# Own_Power_Measuring_Bridge_dev_v1_0_Fina.net
KiCad netlist of a schematic drawn in EAGLE
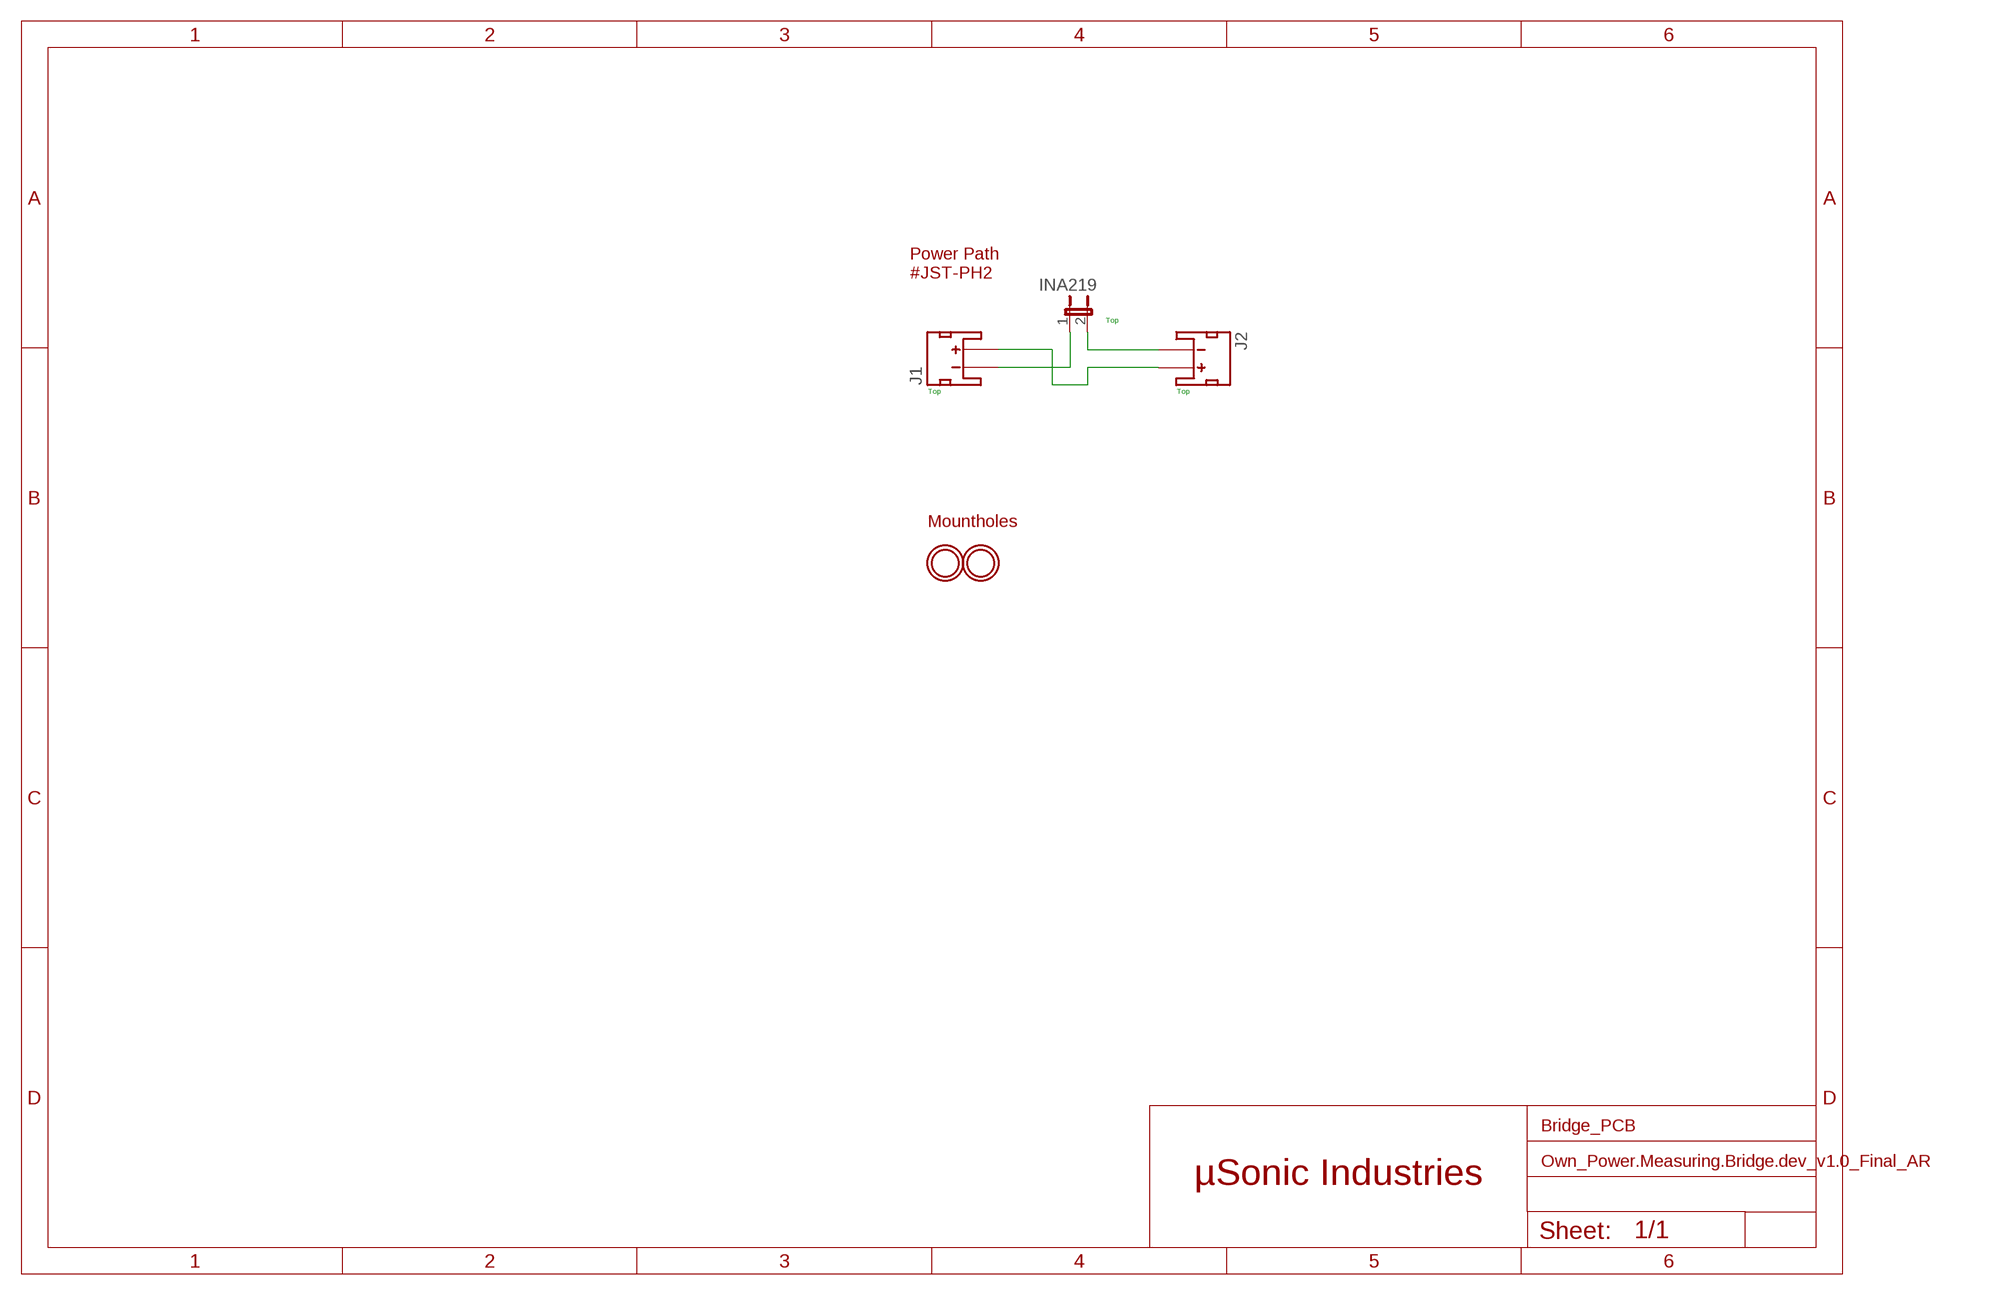
[diagram p0: schematic, sheet 1]

(export (version "E")
  (design (tool "Eeschema 10.0.6"))
  (components
    (comp (ref "INA219")
      (value "JP1E")
      (footprint "eagle-import:JP1")
      (libsource (lib "eagle-import") (part "JP1E"))
    )
    (comp (ref "J1")
      (value "Input")
      (footprint "eagle-import:JST-2-SMD")
      (libsource (lib "eagle-import") (part "JST_2MM_MALE"))
    )
    (comp (ref "J2")
      (value "Output")
      (footprint "eagle-import:JST-2-SMD")
      (libsource (lib "eagle-import") (part "JST_2MM_MALE"))
    )
    (comp (ref "U$18")
      (value "MOUNTINGHOLE2.5")
      (footprint "eagle-import:MOUNTINGHOLE_2.5_PLATED")
      (libsource (lib "eagle-import") (part "MOUNTINGHOLE2.5"))
    )
    (comp (ref "U$19")
      (value "MOUNTINGHOLE2.5")
      (footprint "eagle-import:MOUNTINGHOLE_2.5_PLATED")
      (libsource (lib "eagle-import") (part "MOUNTINGHOLE2.5"))
    )
  )
  (nets
    (net (code "1") (name "Net-(J1-+)") (class "Default")
      (node (ref "J1") (pin "2") (pinfunction "+_2") (pintype "bidirectional"))
      (node (ref "J2") (pin "2") (pinfunction "+_2") (pintype "bidirectional"))
    )
    (net (code "2") (name "Net-(J1--)") (class "Default")
      (node (ref "INA219") (pin "1") (pinfunction "1_1") (pintype "passive"))
      (node (ref "J1") (pin "1") (pinfunction "-_1") (pintype "bidirectional"))
    )
    (net (code "3") (name "Net-(J2--)") (class "Default")
      (node (ref "INA219") (pin "2") (pinfunction "2_2") (pintype "passive"))
      (node (ref "J2") (pin "1") (pinfunction "-_1") (pintype "bidirectional"))
    )
    (net (code "4") (name "unconnected-(J1-PAD1-PadNC1)") (class "Default")
      (node (ref "J1") (pin "NC1") (pinfunction "PAD1_NC1") (pintype "bidirectional"))
    )
    (net (code "5") (name "unconnected-(J1-PAD2-PadNC2)") (class "Default")
      (node (ref "J1") (pin "NC2") (pinfunction "PAD2_NC2") (pintype "bidirectional"))
    )
    (net (code "6") (name "unconnected-(J2-PAD1-PadNC1)") (class "Default")
      (node (ref "J2") (pin "NC1") (pinfunction "PAD1_NC1") (pintype "bidirectional"))
    )
    (net (code "7") (name "unconnected-(J2-PAD2-PadNC2)") (class "Default")
      (node (ref "J2") (pin "NC2") (pinfunction "PAD2_NC2") (pintype "bidirectional"))
    )
  )
)
